# ISO_Signals.net
KiCad netlist of a schematic drawn in Altium Designer
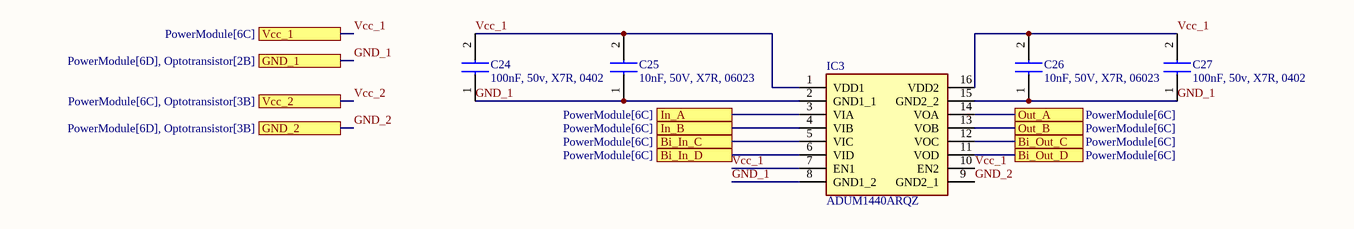
[diagram p0: ISO_Signals.SchDoc]

(export (version "E")
  (design (tool "Eeschema 10.0.6"))
  (components
    (comp (ref "C24")
      (value "100nF, 50v, X7R, 0402")
      (footprint "SamacSys:CAPC2012X88N")
      (description "Capacitor")
      (fields
        (field (name "MANUFACTURER_PART_NUMBER") "C0805C104M5RAC")
        (field (name "MOUSER PART NUMBER") "80-C0805C104M5RAC")
      )
      (libsource (lib "*") (part "C0805C104M5RAC"))
    )
    (comp (ref "C25")
      (value "10nF, 50V, X7R, 06023")
      (footprint "SamacSys:CAPC1608X87N")
      (description "Capacitor")
      (fields
        (field (name "MANUFACTURER_PART_NUMBER") "C0603C103J5RAC")
        (field (name "MOUSER PART NUMBER") "80-C0603C103J5RAC")
      )
      (libsource (lib "*") (part "C0603C103J5RAC"))
    )
    (comp (ref "C26")
      (value "10nF, 50V, X7R, 06023")
      (footprint "SamacSys:CAPC1608X87N")
      (description "Capacitor")
      (fields
        (field (name "MANUFACTURER_PART_NUMBER") "C0603C103J5RAC")
        (field (name "MOUSER PART NUMBER") "80-C0603C103J5RAC")
      )
      (libsource (lib "*") (part "C0603C103J5RAC"))
    )
    (comp (ref "C27")
      (value "100nF, 50v, X7R, 0402")
      (footprint "SamacSys:CAPC2012X88N")
      (description "Capacitor")
      (fields
        (field (name "MANUFACTURER_PART_NUMBER") "C0805C104M5RAC")
        (field (name "MOUSER PART NUMBER") "80-C0805C104M5RAC")
      )
      (libsource (lib "*") (part "C0805C104M5RAC"))
    )
    (comp (ref "IC3")
      (value "ADUM1440ARQZ")
      (footprint "SamacSys:SOP64P600X175-16N")
      (description "Integrated Circuit")
      (fields (field (name "MOUSER PART NUMBER") "584-ADUM1440ARQZ"))
      (libsource (lib "*") (part "ADUM1440ARQZ"))
    )
  )
  (nets
    (net (code "1") (name "/Bi_In_C") (class "Default")
      (node (ref "IC3") (pin "5") (pinfunction "VIC_5") (pintype "passive"))
    )
    (net (code "2") (name "/Bi_In_D") (class "Default")
      (node (ref "IC3") (pin "6") (pinfunction "VID_6") (pintype "passive"))
    )
    (net (code "3") (name "/Bi_Out_C") (class "Default")
      (node (ref "IC3") (pin "12") (pinfunction "VOC_12") (pintype "passive"))
    )
    (net (code "4") (name "/Bi_Out_D") (class "Default")
      (node (ref "IC3") (pin "11") (pinfunction "VOD_11") (pintype "passive"))
    )
    (net (code "5") (name "/GND_1") (class "Default")
      (node (ref "C24") (pin "1") (pinfunction "1_1") (pintype "passive"))
      (node (ref "C25") (pin "1") (pinfunction "1_1") (pintype "passive"))
      (node (ref "C26") (pin "1") (pinfunction "1_1") (pintype "passive"))
      (node (ref "C27") (pin "1") (pinfunction "1_1") (pintype "passive"))
      (node (ref "IC3") (pin "15") (pinfunction "GND2_2_15") (pintype "passive"))
      (node (ref "IC3") (pin "2") (pinfunction "GND1_1_2") (pintype "passive"))
      (node (ref "IC3") (pin "8") (pinfunction "GND1_2_8") (pintype "passive"))
    )
    (net (code "6") (name "/GND_2") (class "Default")
      (node (ref "IC3") (pin "9") (pinfunction "GND2_1_9") (pintype "passive"))
    )
    (net (code "7") (name "/In_A") (class "Default")
      (node (ref "IC3") (pin "3") (pinfunction "VIA_3") (pintype "passive"))
    )
    (net (code "8") (name "/In_B") (class "Default")
      (node (ref "IC3") (pin "4") (pinfunction "VIB_4") (pintype "passive"))
    )
    (net (code "9") (name "/Out_A") (class "Default")
      (node (ref "IC3") (pin "14") (pinfunction "VOA_14") (pintype "passive"))
    )
    (net (code "10") (name "/Out_B") (class "Default")
      (node (ref "IC3") (pin "13") (pinfunction "VOB_13") (pintype "passive"))
    )
    (net (code "11") (name "/Vcc_1") (class "Default")
      (node (ref "C24") (pin "2") (pinfunction "2_2") (pintype "passive"))
      (node (ref "C25") (pin "2") (pinfunction "2_2") (pintype "passive"))
      (node (ref "C26") (pin "2") (pinfunction "2_2") (pintype "passive"))
      (node (ref "C27") (pin "2") (pinfunction "2_2") (pintype "passive"))
      (node (ref "IC3") (pin "1") (pinfunction "VDD1_1") (pintype "passive"))
      (node (ref "IC3") (pin "10") (pinfunction "EN2_10") (pintype "passive"))
      (node (ref "IC3") (pin "16") (pinfunction "VDD2_16") (pintype "passive"))
      (node (ref "IC3") (pin "7") (pinfunction "EN1_7") (pintype "passive"))
    )
  )
)
